# Sheet7.net
KiCad netlist of a schematic drawn in Altium Designer
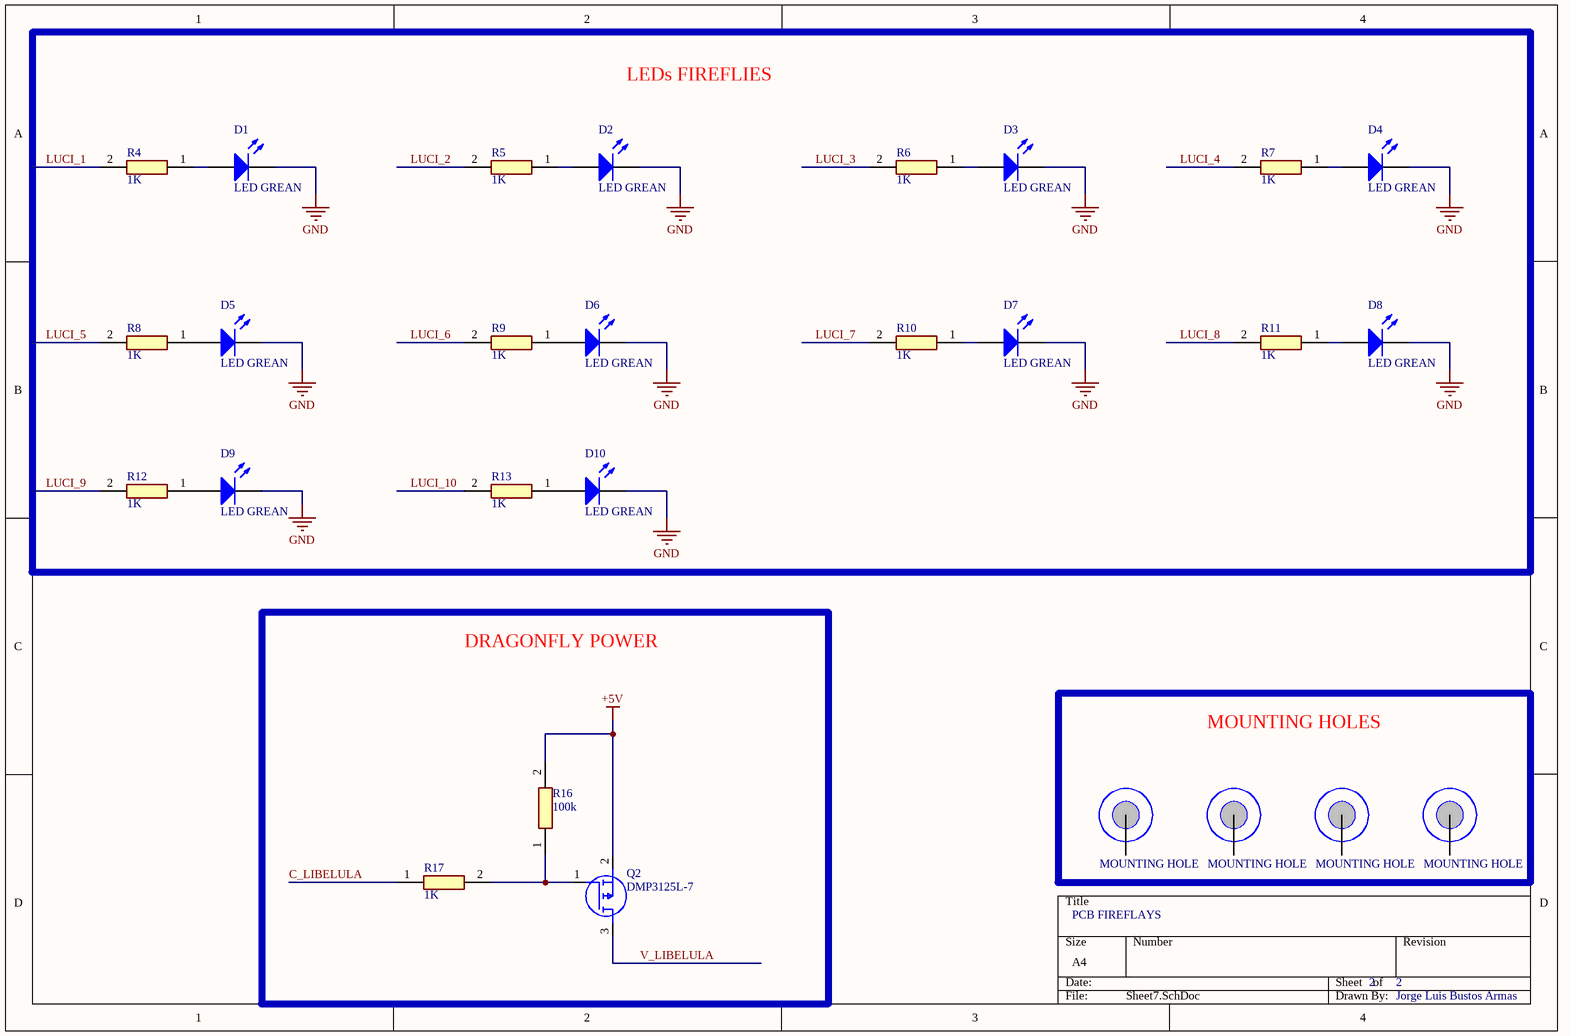
[diagram p0: Sheet7.SchDoc]

(export (version "E")
  (design (tool "Eeschema 10.0.6"))
  (components
    (comp (ref "D1")
      (value "LED GREAN")
      (footprint "ARDUINO_NANO:LED 5mm")
      (description "Typical GREAN LED")
      (fields (field (name "PUBLISHER") "Altium Limited"))
      (libsource (lib "Miscellaneous Devices") (part "LED1"))
    )
    (comp (ref "D2")
      (value "LED GREAN")
      (footprint "ARDUINO_NANO:LED 5mm")
      (description "Typical GREAN LED")
      (fields (field (name "PUBLISHER") "Altium Limited"))
      (libsource (lib "Miscellaneous Devices") (part "LED1"))
    )
    (comp (ref "D3")
      (value "LED GREAN")
      (footprint "ARDUINO_NANO:LED 5mm")
      (description "Typical GREAN LED")
      (fields (field (name "PUBLISHER") "Altium Limited"))
      (libsource (lib "Miscellaneous Devices") (part "LED1"))
    )
    (comp (ref "D4")
      (value "LED GREAN")
      (footprint "ARDUINO_NANO:LED 5mm")
      (description "Typical GREAN LED")
      (fields (field (name "PUBLISHER") "Altium Limited"))
      (libsource (lib "Miscellaneous Devices") (part "LED1"))
    )
    (comp (ref "D5")
      (value "LED GREAN")
      (footprint "ARDUINO_NANO:LED 5mm")
      (description "Typical GREAN LED")
      (fields (field (name "PUBLISHER") "Altium Limited"))
      (libsource (lib "Miscellaneous Devices") (part "LED1"))
    )
    (comp (ref "D6")
      (value "LED GREAN")
      (footprint "ARDUINO_NANO:LED 5mm")
      (description "Typical GREAN LED")
      (fields (field (name "PUBLISHER") "Altium Limited"))
      (libsource (lib "Miscellaneous Devices") (part "LED1"))
    )
    (comp (ref "D7")
      (value "LED GREAN")
      (footprint "ARDUINO_NANO:LED 5mm")
      (description "Typical GREAN LED")
      (fields (field (name "PUBLISHER") "Altium Limited"))
      (libsource (lib "Miscellaneous Devices") (part "LED1"))
    )
    (comp (ref "D8")
      (value "LED GREAN")
      (footprint "ARDUINO_NANO:LED 5mm")
      (description "Typical GREAN LED")
      (fields (field (name "PUBLISHER") "Altium Limited"))
      (libsource (lib "Miscellaneous Devices") (part "LED1"))
    )
    (comp (ref "D9")
      (value "LED GREAN")
      (footprint "ARDUINO_NANO:LED 5mm")
      (description "Typical GREAN LED")
      (fields (field (name "PUBLISHER") "Altium Limited"))
      (libsource (lib "Miscellaneous Devices") (part "LED1"))
    )
    (comp (ref "D10")
      (value "LED GREAN")
      (footprint "ARDUINO_NANO:LED 5mm")
      (description "Typical GREAN LED")
      (fields (field (name "PUBLISHER") "Altium Limited"))
      (libsource (lib "Miscellaneous Devices") (part "LED1"))
    )
    (comp (ref "MH1")
      (value "MOUNTING HOLE")
      (footprint "MH")
      (libsource (lib "ARDUINO_NANO") (part "MOUNTING HOLE"))
    )
    (comp (ref "MH2")
      (value "MOUNTING HOLE")
      (footprint "MH")
      (libsource (lib "ARDUINO_NANO") (part "MOUNTING HOLE"))
    )
    (comp (ref "MH3")
      (value "MOUNTING HOLE")
      (footprint "MH")
      (libsource (lib "ARDUINO_NANO") (part "MOUNTING HOLE"))
    )
    (comp (ref "MH4")
      (value "MOUNTING HOLE")
      (footprint "MH")
      (libsource (lib "ARDUINO_NANO") (part "MOUNTING HOLE"))
    )
    (comp (ref "Q2")
      (value "DMP3125L-7")
      (footprint "SamacSys:SOT96P240X110-3N")
      (description "MOSFET (P-Channel)")
      (fields (field (name "MOUSER PART NUMBER") "621-DMP3125L-7"))
      (libsource (lib "SamacSys") (part "DMP3125L-7"))
    )
    (comp (ref "R4")
      (value "1K")
      (footprint "SamacSys:RESC1608X55N")
      (description "Resistor")
      (fields
        (field (name "MANUFACTURER_PART_NUMBER") "KTR03EZPF1501")
        (field (name "MOUSER PART NUMBER") "755-KTR03EZPF1501")
      )
      (libsource (lib "SamacSys") (part "KTR03EZPF1501"))
    )
    (comp (ref "R5")
      (value "1K")
      (footprint "SamacSys:RESC1608X55N")
      (description "Resistor")
      (fields
        (field (name "MANUFACTURER_PART_NUMBER") "KTR03EZPF1501")
        (field (name "MOUSER PART NUMBER") "755-KTR03EZPF1501")
      )
      (libsource (lib "SamacSys") (part "KTR03EZPF1501"))
    )
    (comp (ref "R6")
      (value "1K")
      (footprint "SamacSys:RESC1608X55N")
      (description "Resistor")
      (fields
        (field (name "MANUFACTURER_PART_NUMBER") "KTR03EZPF1501")
        (field (name "MOUSER PART NUMBER") "755-KTR03EZPF1501")
      )
      (libsource (lib "SamacSys") (part "KTR03EZPF1501"))
    )
    (comp (ref "R7")
      (value "1K")
      (footprint "SamacSys:RESC1608X55N")
      (description "Resistor")
      (fields
        (field (name "MANUFACTURER_PART_NUMBER") "KTR03EZPF1501")
        (field (name "MOUSER PART NUMBER") "755-KTR03EZPF1501")
      )
      (libsource (lib "SamacSys") (part "KTR03EZPF1501"))
    )
    (comp (ref "R8")
      (value "1K")
      (footprint "SamacSys:RESC1608X55N")
      (description "Resistor")
      (fields
        (field (name "MANUFACTURER_PART_NUMBER") "KTR03EZPF1501")
        (field (name "MOUSER PART NUMBER") "755-KTR03EZPF1501")
      )
      (libsource (lib "SamacSys") (part "KTR03EZPF1501"))
    )
    (comp (ref "R9")
      (value "1K")
      (footprint "SamacSys:RESC1608X55N")
      (description "Resistor")
      (fields
        (field (name "MANUFACTURER_PART_NUMBER") "KTR03EZPF1501")
        (field (name "MOUSER PART NUMBER") "755-KTR03EZPF1501")
      )
      (libsource (lib "SamacSys") (part "KTR03EZPF1501"))
    )
    (comp (ref "R10")
      (value "1K")
      (footprint "SamacSys:RESC1608X55N")
      (description "Resistor")
      (fields
        (field (name "MANUFACTURER_PART_NUMBER") "KTR03EZPF1501")
        (field (name "MOUSER PART NUMBER") "755-KTR03EZPF1501")
      )
      (libsource (lib "SamacSys") (part "KTR03EZPF1501"))
    )
    (comp (ref "R11")
      (value "1K")
      (footprint "SamacSys:RESC1608X55N")
      (description "Resistor")
      (fields
        (field (name "MANUFACTURER_PART_NUMBER") "KTR03EZPF1501")
        (field (name "MOUSER PART NUMBER") "755-KTR03EZPF1501")
      )
      (libsource (lib "SamacSys") (part "KTR03EZPF1501"))
    )
    (comp (ref "R12")
      (value "1K")
      (footprint "SamacSys:RESC1608X55N")
      (description "Resistor")
      (fields
        (field (name "MANUFACTURER_PART_NUMBER") "KTR03EZPF1501")
        (field (name "MOUSER PART NUMBER") "755-KTR03EZPF1501")
      )
      (libsource (lib "SamacSys") (part "KTR03EZPF1501"))
    )
    (comp (ref "R13")
      (value "1K")
      (footprint "SamacSys:RESC1608X55N")
      (description "Resistor")
      (fields
        (field (name "MANUFACTURER_PART_NUMBER") "KTR03EZPF1501")
        (field (name "MOUSER PART NUMBER") "755-KTR03EZPF1501")
      )
      (libsource (lib "SamacSys") (part "KTR03EZPF1501"))
    )
    (comp (ref "R16")
      (value "100k")
      (footprint "SamacSys:RESC1608X55N")
      (description "Resistor")
      (fields
        (field (name "MANUFACTURER_PART_NUMBER") "KTR03EZPF1501")
        (field (name "MOUSER PART NUMBER") "755-KTR03EZPF1501")
      )
      (libsource (lib "") (part "KTR03EZPF1501_1"))
    )
    (comp (ref "R17")
      (value "1K")
      (footprint "SamacSys:RESC1608X55N")
      (description "Resistor")
      (fields
        (field (name "MANUFACTURER_PART_NUMBER") "KTR03EZPF1501")
        (field (name "MOUSER PART NUMBER") "755-KTR03EZPF1501")
      )
      (libsource (lib "") (part "KTR03EZPF1501_2"))
    )
  )
  (nets
    (net (code "1") (name "+5V") (class "Default")
      (node (ref "Q2") (pin "2") (pinfunction "S_2") (pintype "passive"))
      (node (ref "R16") (pin "2") (pinfunction "2_2") (pintype "passive"))
    )
    (net (code "2") (name "/C_LIBELULA") (class "Default")
      (node (ref "R17") (pin "1") (pinfunction "1_1") (pintype "passive"))
    )
    (net (code "3") (name "/LUCI_1") (class "Default")
      (node (ref "R4") (pin "2") (pinfunction "2_2") (pintype "passive"))
    )
    (net (code "4") (name "/LUCI_2") (class "Default")
      (node (ref "R5") (pin "2") (pinfunction "2_2") (pintype "passive"))
    )
    (net (code "5") (name "/LUCI_3") (class "Default")
      (node (ref "R6") (pin "2") (pinfunction "2_2") (pintype "passive"))
    )
    (net (code "6") (name "/LUCI_4") (class "Default")
      (node (ref "R7") (pin "2") (pinfunction "2_2") (pintype "passive"))
    )
    (net (code "7") (name "/LUCI_5") (class "Default")
      (node (ref "R8") (pin "2") (pinfunction "2_2") (pintype "passive"))
    )
    (net (code "8") (name "/LUCI_6") (class "Default")
      (node (ref "R9") (pin "2") (pinfunction "2_2") (pintype "passive"))
    )
    (net (code "9") (name "/LUCI_7") (class "Default")
      (node (ref "R10") (pin "2") (pinfunction "2_2") (pintype "passive"))
    )
    (net (code "10") (name "/LUCI_8") (class "Default")
      (node (ref "R11") (pin "2") (pinfunction "2_2") (pintype "passive"))
    )
    (net (code "11") (name "/LUCI_9") (class "Default")
      (node (ref "R12") (pin "2") (pinfunction "2_2") (pintype "passive"))
    )
    (net (code "12") (name "/LUCI_10") (class "Default")
      (node (ref "R13") (pin "2") (pinfunction "2_2") (pintype "passive"))
    )
    (net (code "13") (name "/V_LIBELULA") (class "Default")
      (node (ref "Q2") (pin "3") (pinfunction "D_3") (pintype "passive"))
    )
    (net (code "14") (name "GND") (class "Default")
      (node (ref "D1") (pin "2") (pinfunction "K_2") (pintype "passive"))
      (node (ref "D10") (pin "2") (pinfunction "K_2") (pintype "passive"))
      (node (ref "D2") (pin "2") (pinfunction "K_2") (pintype "passive"))
      (node (ref "D3") (pin "2") (pinfunction "K_2") (pintype "passive"))
      (node (ref "D4") (pin "2") (pinfunction "K_2") (pintype "passive"))
      (node (ref "D5") (pin "2") (pinfunction "K_2") (pintype "passive"))
      (node (ref "D6") (pin "2") (pinfunction "K_2") (pintype "passive"))
      (node (ref "D7") (pin "2") (pinfunction "K_2") (pintype "passive"))
      (node (ref "D8") (pin "2") (pinfunction "K_2") (pintype "passive"))
      (node (ref "D9") (pin "2") (pinfunction "K_2") (pintype "passive"))
    )
    (net (code "15") (name "Net-(D1-A)") (class "Default")
      (node (ref "D1") (pin "1") (pinfunction "A_1") (pintype "passive"))
      (node (ref "R4") (pin "1") (pinfunction "1_1") (pintype "passive"))
    )
    (net (code "16") (name "Net-(D2-A)") (class "Default")
      (node (ref "D2") (pin "1") (pinfunction "A_1") (pintype "passive"))
      (node (ref "R5") (pin "1") (pinfunction "1_1") (pintype "passive"))
    )
    (net (code "17") (name "Net-(D3-A)") (class "Default")
      (node (ref "D3") (pin "1") (pinfunction "A_1") (pintype "passive"))
      (node (ref "R6") (pin "1") (pinfunction "1_1") (pintype "passive"))
    )
    (net (code "18") (name "Net-(D4-A)") (class "Default")
      (node (ref "D4") (pin "1") (pinfunction "A_1") (pintype "passive"))
      (node (ref "R7") (pin "1") (pinfunction "1_1") (pintype "passive"))
    )
    (net (code "19") (name "Net-(D5-A)") (class "Default")
      (node (ref "D5") (pin "1") (pinfunction "A_1") (pintype "passive"))
      (node (ref "R8") (pin "1") (pinfunction "1_1") (pintype "passive"))
    )
    (net (code "20") (name "Net-(D6-A)") (class "Default")
      (node (ref "D6") (pin "1") (pinfunction "A_1") (pintype "passive"))
      (node (ref "R9") (pin "1") (pinfunction "1_1") (pintype "passive"))
    )
    (net (code "21") (name "Net-(D7-A)") (class "Default")
      (node (ref "D7") (pin "1") (pinfunction "A_1") (pintype "passive"))
      (node (ref "R10") (pin "1") (pinfunction "1_1") (pintype "passive"))
    )
    (net (code "22") (name "Net-(D8-A)") (class "Default")
      (node (ref "D8") (pin "1") (pinfunction "A_1") (pintype "passive"))
      (node (ref "R11") (pin "1") (pinfunction "1_1") (pintype "passive"))
    )
    (net (code "23") (name "Net-(D9-A)") (class "Default")
      (node (ref "D9") (pin "1") (pinfunction "A_1") (pintype "passive"))
      (node (ref "R12") (pin "1") (pinfunction "1_1") (pintype "passive"))
    )
    (net (code "24") (name "Net-(D10-A)") (class "Default")
      (node (ref "D10") (pin "1") (pinfunction "A_1") (pintype "passive"))
      (node (ref "R13") (pin "1") (pinfunction "1_1") (pintype "passive"))
    )
    (net (code "25") (name "Net-(Q2-G)") (class "Default")
      (node (ref "Q2") (pin "1") (pinfunction "G_1") (pintype "passive"))
      (node (ref "R16") (pin "1") (pinfunction "1_1") (pintype "passive"))
      (node (ref "R17") (pin "2") (pinfunction "2_2") (pintype "passive"))
    )
    (net (code "26") (name "unconnected-(MH1-Pad)") (class "Default")
      (node (ref "MH1") (pin "") (pintype "passive"))
    )
    (net (code "27") (name "unconnected-(MH2-Pad)") (class "Default")
      (node (ref "MH2") (pin "") (pintype "passive"))
    )
    (net (code "28") (name "unconnected-(MH3-Pad)") (class "Default")
      (node (ref "MH3") (pin "") (pintype "passive"))
    )
    (net (code "29") (name "unconnected-(MH4-Pad)") (class "Default")
      (node (ref "MH4") (pin "") (pintype "passive"))
    )
  )
)
